# PowerSystem.net
KiCad netlist of a schematic drawn in EAGLE
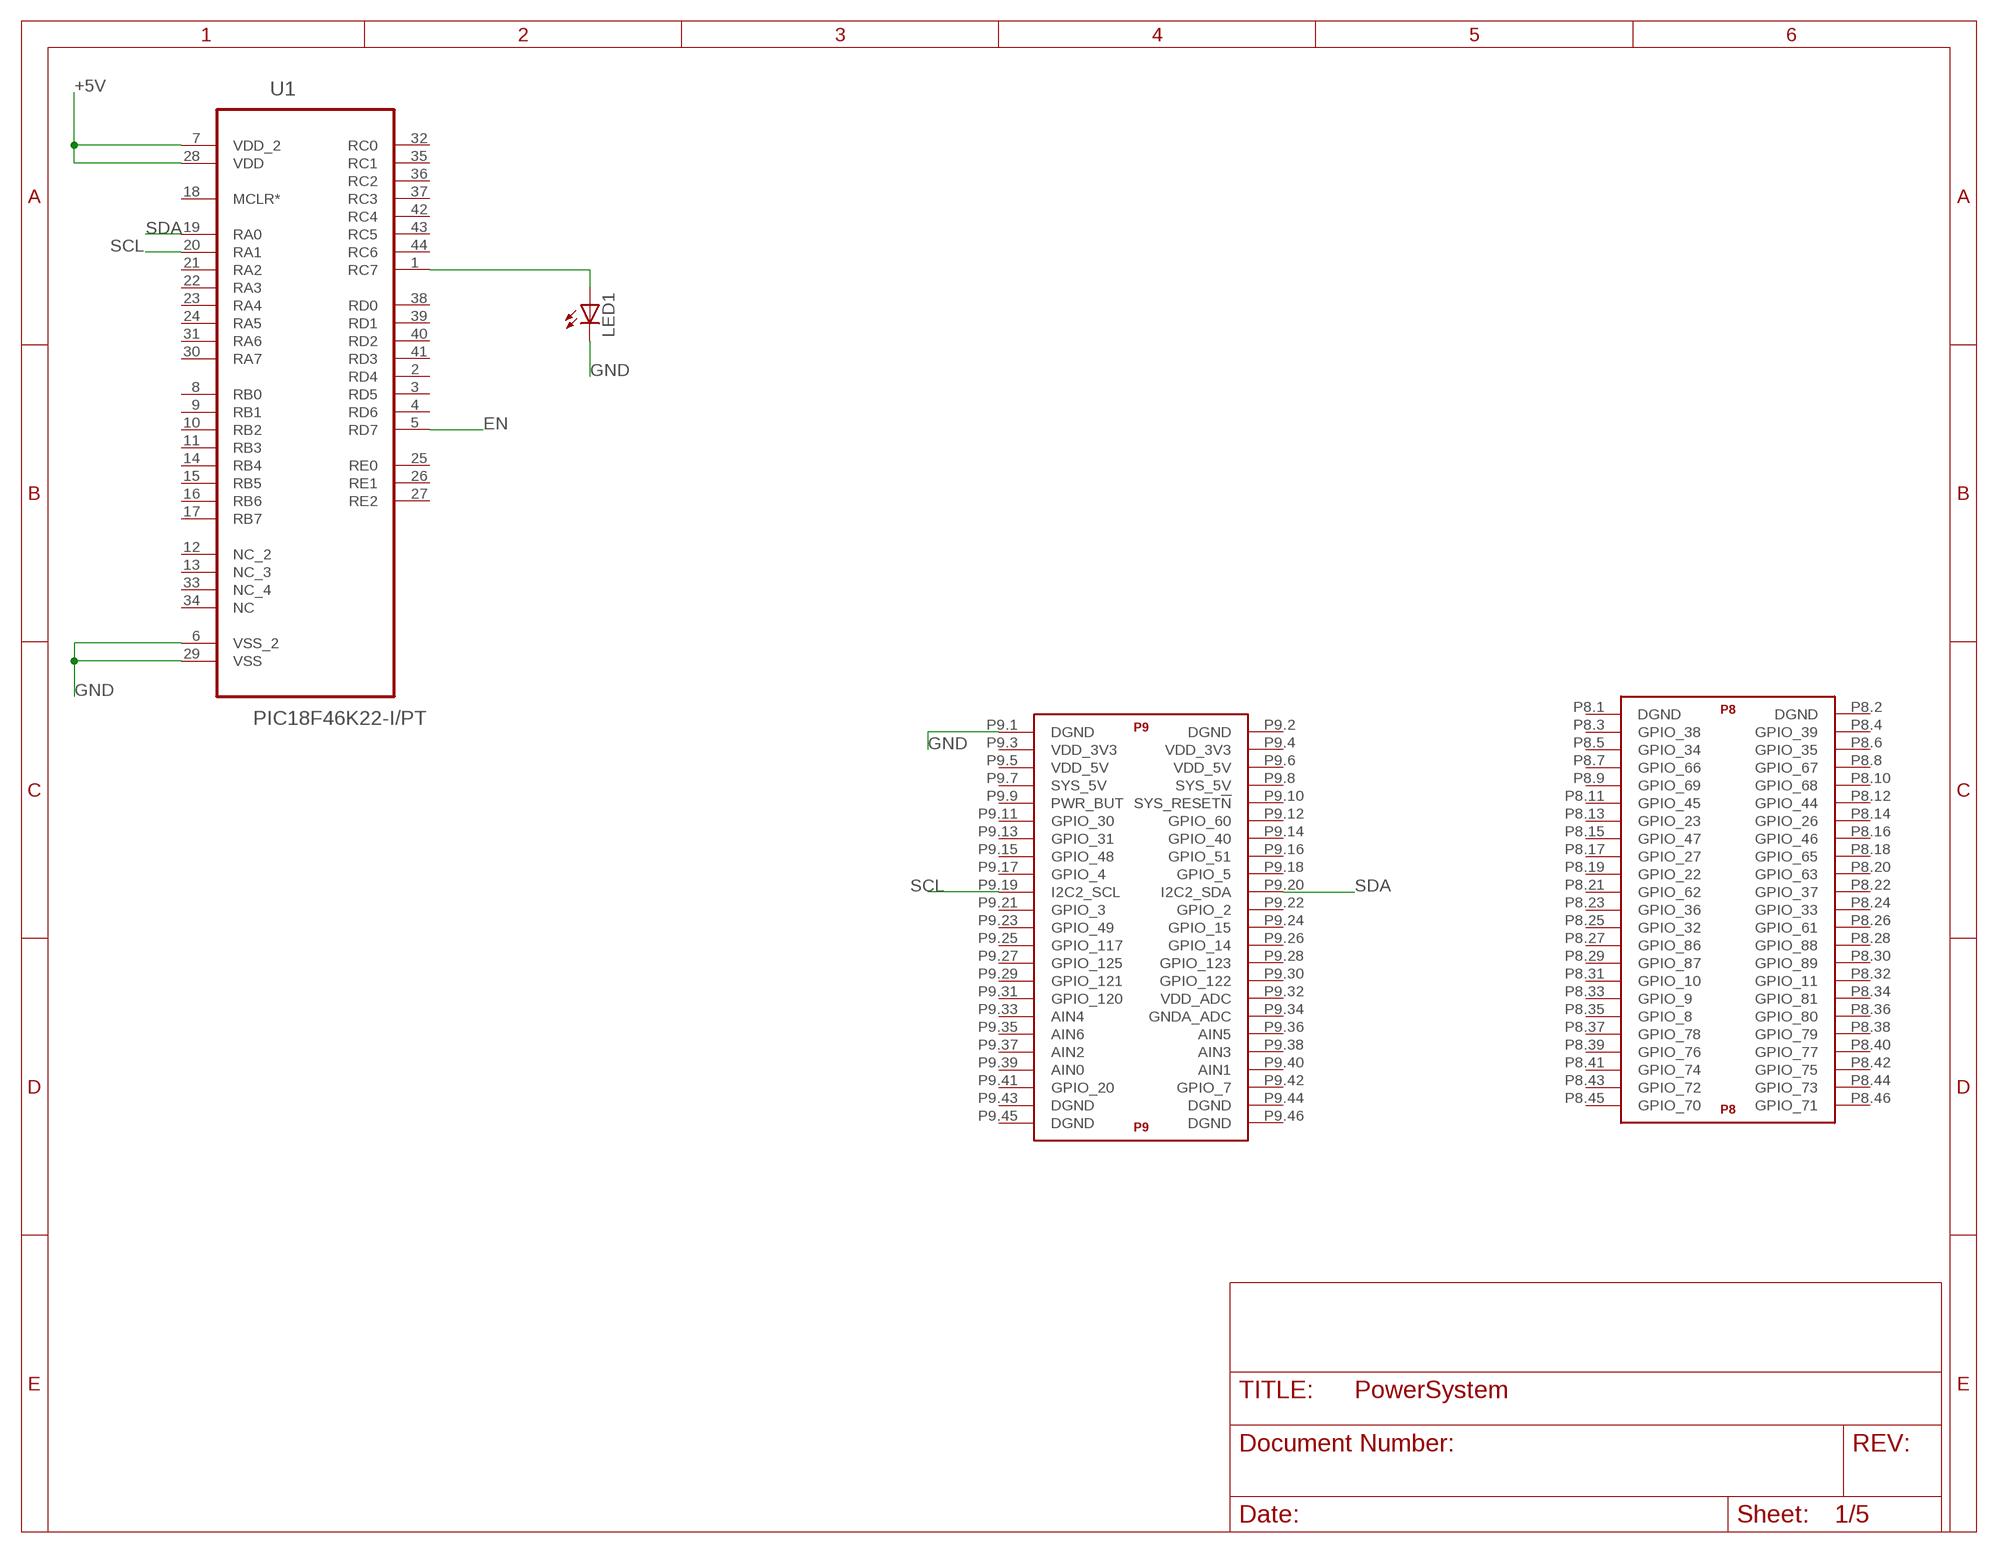
[diagram p0: schematic, sheet 1]
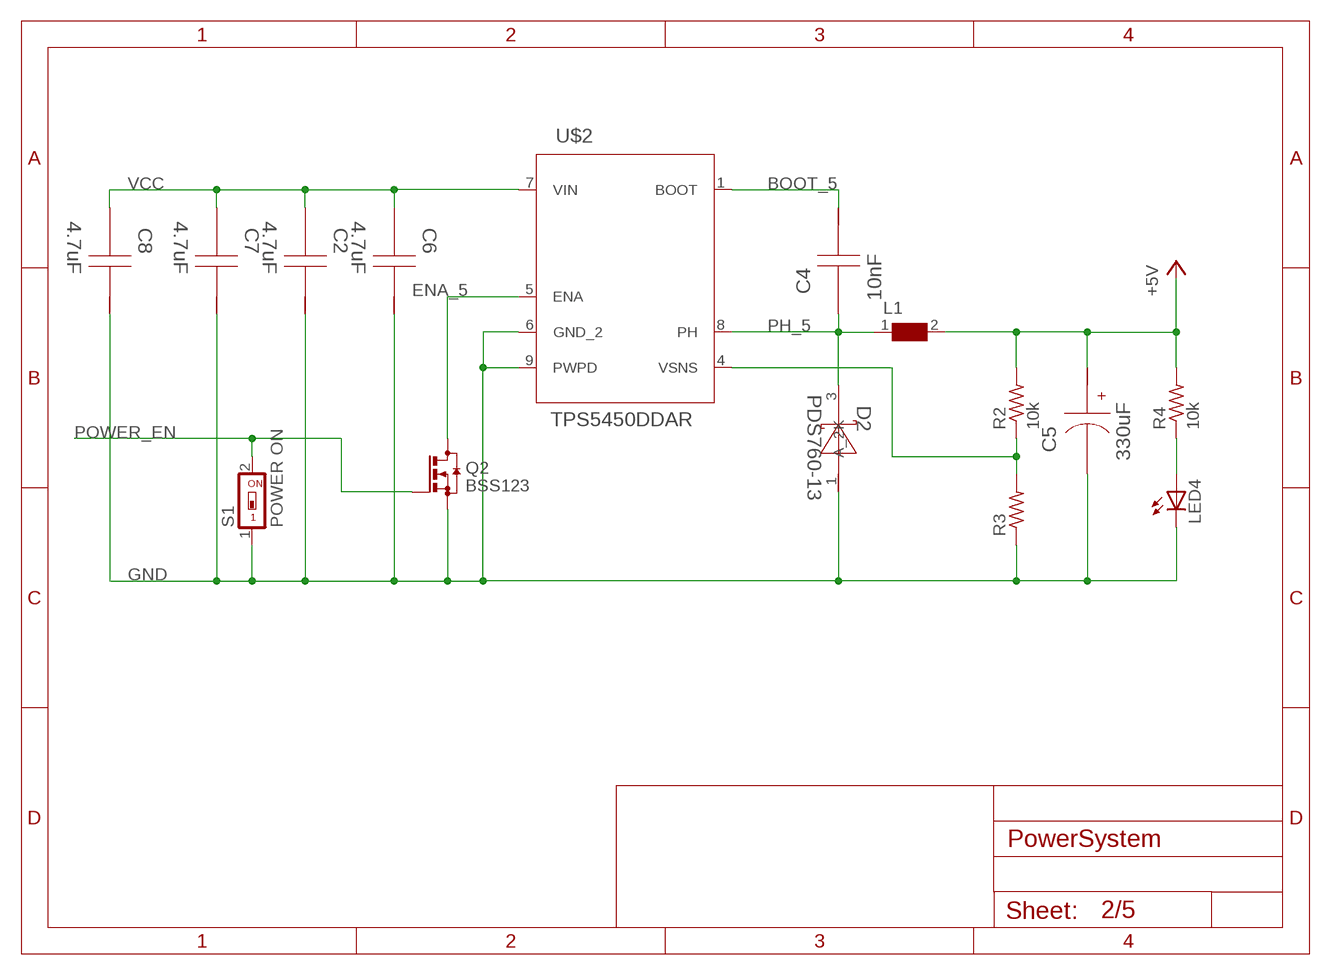
[diagram p1: schematic, sheet 2]
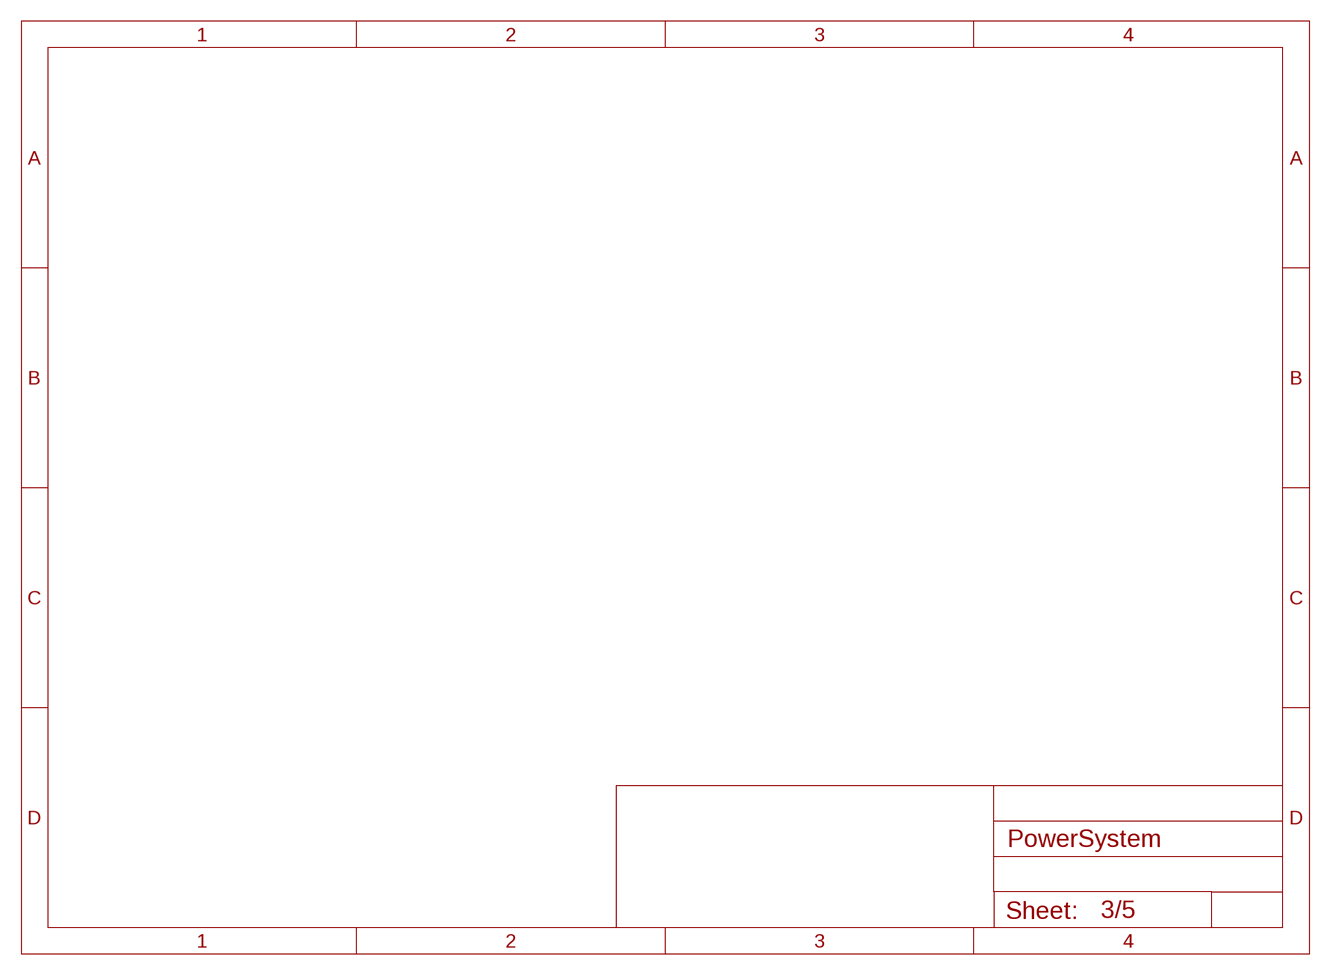
[diagram p2: schematic, sheet 3]
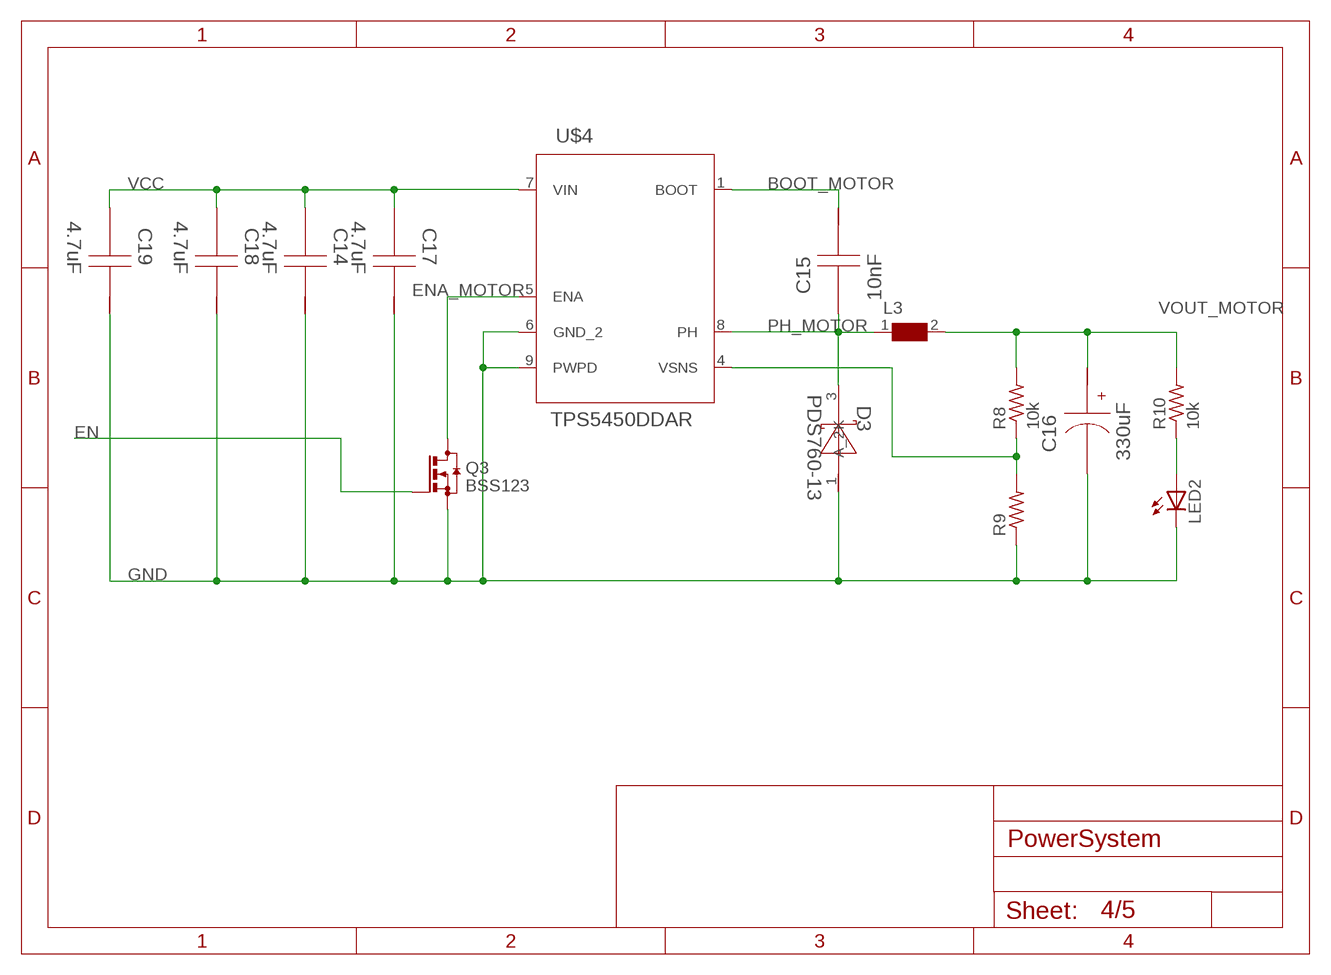
[diagram p3: schematic, sheet 4]
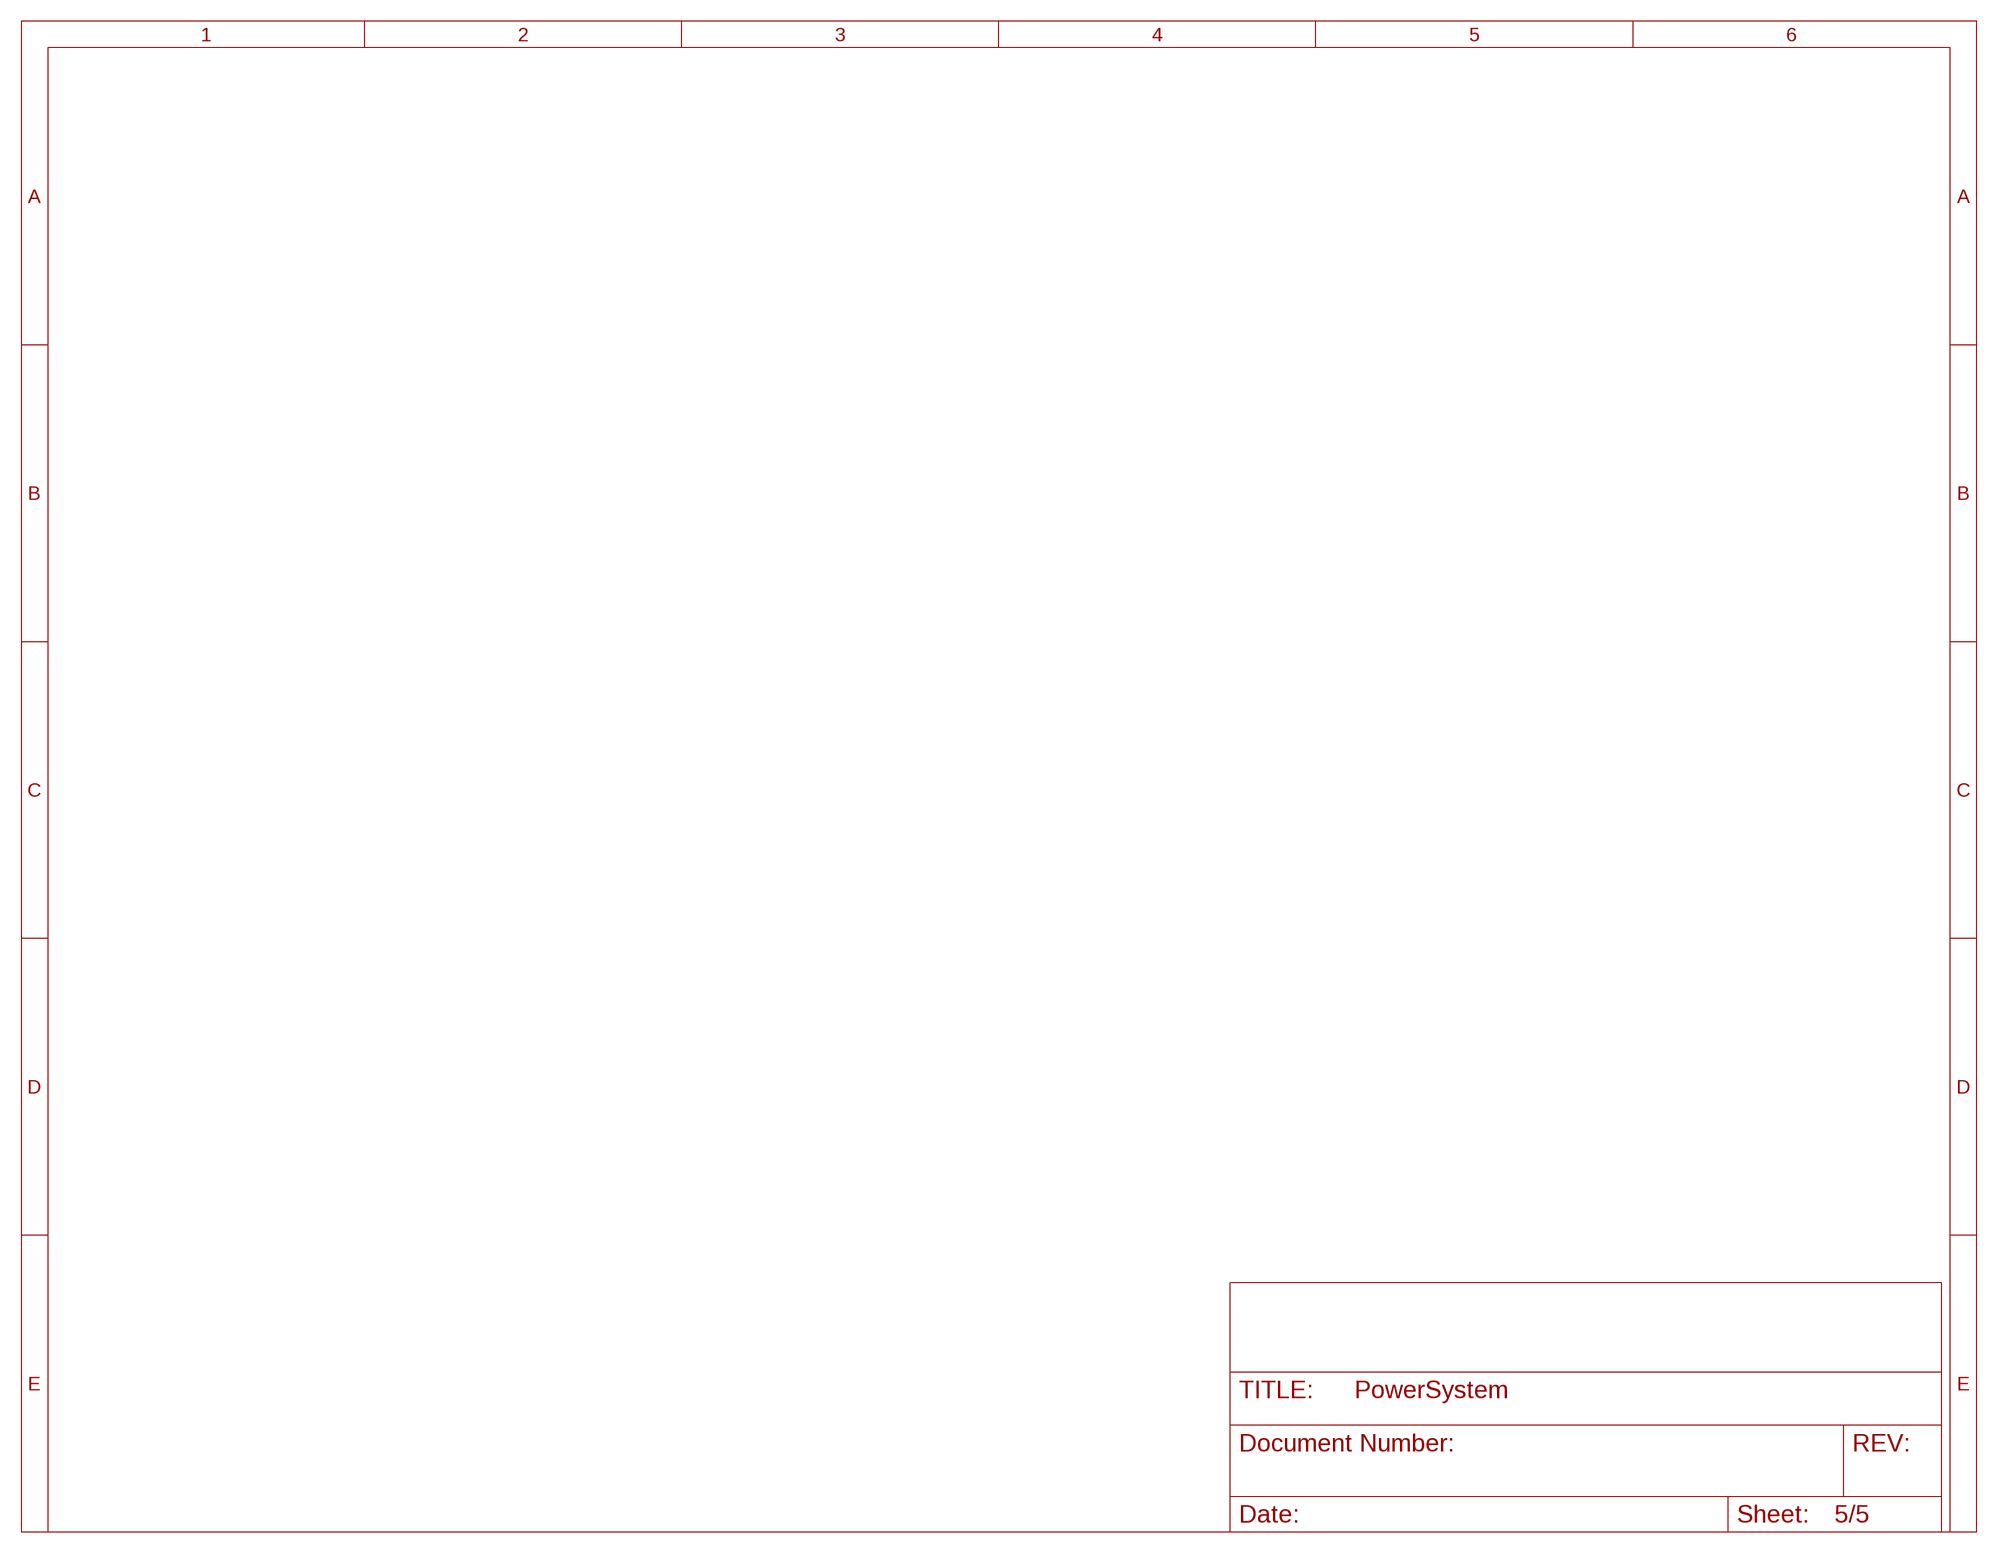
[diagram p4: schematic, sheet 5]

(export (version "E")
  (design (tool "Eeschema 10.0.6"))
  (components
    (comp (ref "C2")
      (value "4.7uF")
      (footprint "eagle-import:1206")
      (fields (field (name "MANUFACTURER_PART_NUMBER") "GRM31CR71H475KA12L"))
      (libsource (lib "eagle-import") (part "GRM31CR71H475KA12L"))
    )
    (comp (ref "C4")
      (value "10nF")
      (footprint "eagle-import:0805")
      (fields (field (name "MANUFACTURER_PART_NUMBER") "C0805C103K5RACTU"))
      (libsource (lib "eagle-import") (part "C0805C103K5RACTU"))
    )
    (comp (ref "C5")
      (value "330uF")
      (footprint "eagle-import:SM_RADIAL_10AMM")
      (fields (field (name "MANUFACTURER_PART_NUMBER") "10SVP330MX"))
      (libsource (lib "eagle-import") (part "10SVP330MX"))
    )
    (comp (ref "C6")
      (value "4.7uF")
      (footprint "eagle-import:1206")
      (fields (field (name "MANUFACTURER_PART_NUMBER") "GRM31CR71H475KA12L"))
      (libsource (lib "eagle-import") (part "GRM31CR71H475KA12L"))
    )
    (comp (ref "C7")
      (value "4.7uF")
      (footprint "eagle-import:1206")
      (fields (field (name "MANUFACTURER_PART_NUMBER") "GRM31CR71H475KA12L"))
      (libsource (lib "eagle-import") (part "GRM31CR71H475KA12L"))
    )
    (comp (ref "C8")
      (value "4.7uF")
      (footprint "eagle-import:1206")
      (fields (field (name "MANUFACTURER_PART_NUMBER") "GRM31CR71H475KA12L"))
      (libsource (lib "eagle-import") (part "GRM31CR71H475KA12L"))
    )
    (comp (ref "D2")
      (value "PDS760-13")
      (footprint "eagle-import:POWERDI5")
      (libsource (lib "eagle-import") (part "PDS760-13"))
    )
    (comp (ref "L1")
      (value "WE-HCC-7443331000_1090")
      (footprint "eagle-import:WE-HCC_1090")
      (fields (field (name "MPN") "7443331000"))
      (libsource (lib "eagle-import") (part "WE-HCC_1090-7443331000"))
    )
    (comp (ref "LED4")
      (value "LEDSML1206")
      (footprint "eagle-import:SML1206")
      (libsource (lib "eagle-import") (part "led_LEDSML1206"))
    )
    (comp (ref "Q2")
      (value "BSS123")
      (footprint "eagle-import:SOT23")
      (libsource (lib "eagle-import") (part "BSS123"))
    )
    (comp (ref "R2")
      (value "10k")
      (footprint "eagle-import:R1206")
      (libsource (lib "eagle-import") (part "R-US_R1206"))
    )
    (comp (ref "R3")
      (value "R-US_R1206")
      (footprint "eagle-import:R1206")
      (libsource (lib "eagle-import") (part "R-US_R1206"))
    )
    (comp (ref "R4")
      (value "10k")
      (footprint "eagle-import:R1206")
      (libsource (lib "eagle-import") (part "R-US_R1206"))
    )
    (comp (ref "S1")
      (value "POWER ON")
      (footprint "eagle-import:SMS-001")
      (libsource (lib "eagle-import") (part "SWS001"))
    )
    (comp (ref "U$2")
      (value "TPS5450DDAR")
      (footprint "eagle-import:R-PDSO-G8")
      (fields (field (name "MANUFACTURER_PART_NUMBER") "TPS5450DDA"))
      (libsource (lib "eagle-import") (part "TPS5450DDAR"))
    )
    (comp (ref "LED1")
      (value "LED")
      (footprint "eagle-import:SMARTLED-TTW")
      (libsource (lib "eagle-import") (part "LED"))
    )
    (comp (ref "U$1")
      (value "BEAGLE_BONE_BLACK_CAPE")
      (footprint "eagle-import:BEAGLE_BONE_BLACK_CAPE")
      (libsource (lib "eagle-import") (part "BEAGLE_BONE_BLACK_CAPE"))
    )
    (comp (ref "U1")
      (value "PIC18F46K22-I/PT")
      (footprint "eagle-import:QFP80P1200X1200X120-44N")
      (libsource (lib "eagle-import") (part "PIC18F46K22-I/PT"))
    )
    (comp (ref "C14")
      (value "4.7uF")
      (footprint "eagle-import:1206")
      (fields (field (name "MANUFACTURER_PART_NUMBER") "GRM31CR71H475KA12L"))
      (libsource (lib "eagle-import") (part "GRM31CR71H475KA12L"))
    )
    (comp (ref "C15")
      (value "10nF")
      (footprint "eagle-import:0805")
      (fields (field (name "MANUFACTURER_PART_NUMBER") "C0805C103K5RACTU"))
      (libsource (lib "eagle-import") (part "C0805C103K5RACTU"))
    )
    (comp (ref "C16")
      (value "330uF")
      (footprint "eagle-import:SM_RADIAL_10AMM")
      (fields (field (name "MANUFACTURER_PART_NUMBER") "10SVP330MX"))
      (libsource (lib "eagle-import") (part "10SVP330MX"))
    )
    (comp (ref "C17")
      (value "4.7uF")
      (footprint "eagle-import:1206")
      (fields (field (name "MANUFACTURER_PART_NUMBER") "GRM31CR71H475KA12L"))
      (libsource (lib "eagle-import") (part "GRM31CR71H475KA12L"))
    )
    (comp (ref "C18")
      (value "4.7uF")
      (footprint "eagle-import:1206")
      (fields (field (name "MANUFACTURER_PART_NUMBER") "GRM31CR71H475KA12L"))
      (libsource (lib "eagle-import") (part "GRM31CR71H475KA12L"))
    )
    (comp (ref "C19")
      (value "4.7uF")
      (footprint "eagle-import:1206")
      (fields (field (name "MANUFACTURER_PART_NUMBER") "GRM31CR71H475KA12L"))
      (libsource (lib "eagle-import") (part "GRM31CR71H475KA12L"))
    )
    (comp (ref "D3")
      (value "PDS760-13")
      (footprint "eagle-import:POWERDI5")
      (libsource (lib "eagle-import") (part "PDS760-13"))
    )
    (comp (ref "L3")
      (value "WE-HCC-7443331000_1090")
      (footprint "eagle-import:WE-HCC_1090")
      (fields (field (name "MPN") "7443331000"))
      (libsource (lib "eagle-import") (part "WE-HCC_1090-7443331000"))
    )
    (comp (ref "LED2")
      (value "LEDSML1206")
      (footprint "eagle-import:SML1206")
      (libsource (lib "eagle-import") (part "led_LEDSML1206"))
    )
    (comp (ref "Q3")
      (value "BSS123")
      (footprint "eagle-import:SOT23")
      (libsource (lib "eagle-import") (part "BSS123"))
    )
    (comp (ref "R8")
      (value "10k")
      (footprint "eagle-import:R1206")
      (libsource (lib "eagle-import") (part "R-US_R1206"))
    )
    (comp (ref "R9")
      (value "R-US_R1206")
      (footprint "eagle-import:R1206")
      (libsource (lib "eagle-import") (part "R-US_R1206"))
    )
    (comp (ref "R10")
      (value "10k")
      (footprint "eagle-import:R1206")
      (libsource (lib "eagle-import") (part "R-US_R1206"))
    )
    (comp (ref "U$4")
      (value "TPS5450DDAR")
      (footprint "eagle-import:R-PDSO-G8")
      (fields (field (name "MANUFACTURER_PART_NUMBER") "TPS5450DDA"))
      (libsource (lib "eagle-import") (part "TPS5450DDAR"))
    )
  )
  (nets
    (net (code "1") (name "+5V") (class "Default")
      (node (ref "C5") (pin "1") (pinfunction "+_1") (pintype "passive"))
      (node (ref "L1") (pin "2") (pinfunction "2_2") (pintype "passive"))
      (node (ref "R2") (pin "2") (pinfunction "2_2") (pintype "passive"))
      (node (ref "R4") (pin "2") (pinfunction "2_2") (pintype "passive"))
      (node (ref "U1") (pin "28") (pinfunction "VDD_28") (pintype "power_in"))
      (node (ref "U1") (pin "7") (pinfunction "VDD_2_7") (pintype "power_in"))
    )
    (net (code "2") (name "BOOT_5") (class "Default")
      (node (ref "C4") (pin "1") (pinfunction "1_1") (pintype "passive"))
      (node (ref "U$2") (pin "1") (pinfunction "BOOT_1") (pintype "passive"))
    )
    (net (code "3") (name "BOOT_MOTOR") (class "Default")
      (node (ref "C15") (pin "1") (pinfunction "1_1") (pintype "passive"))
      (node (ref "U$4") (pin "1") (pinfunction "BOOT_1") (pintype "passive"))
    )
    (net (code "4") (name "EN") (class "Default")
      (node (ref "Q3") (pin "1") (pinfunction "G_1") (pintype "passive"))
      (node (ref "U1") (pin "5") (pinfunction "RD7_5") (pintype "bidirectional"))
    )
    (net (code "5") (name "ENA_5") (class "Default")
      (node (ref "Q2") (pin "3") (pinfunction "D_3") (pintype "passive"))
      (node (ref "U$2") (pin "5") (pinfunction "ENA_5") (pintype "passive"))
    )
    (net (code "6") (name "ENA_MOTOR") (class "Default")
      (node (ref "Q3") (pin "3") (pinfunction "D_3") (pintype "passive"))
      (node (ref "U$4") (pin "5") (pinfunction "ENA_5") (pintype "passive"))
    )
    (net (code "7") (name "GND") (class "Default")
      (node (ref "C14") (pin "1") (pinfunction "1_1") (pintype "passive"))
      (node (ref "C16") (pin "2") (pinfunction "-_2") (pintype "passive"))
      (node (ref "C17") (pin "1") (pinfunction "1_1") (pintype "passive"))
      (node (ref "C18") (pin "1") (pinfunction "1_1") (pintype "passive"))
      (node (ref "C19") (pin "1") (pinfunction "1_1") (pintype "passive"))
      (node (ref "C2") (pin "1") (pinfunction "1_1") (pintype "passive"))
      (node (ref "C5") (pin "2") (pinfunction "-_2") (pintype "passive"))
      (node (ref "C6") (pin "1") (pinfunction "1_1") (pintype "passive"))
      (node (ref "C7") (pin "1") (pinfunction "1_1") (pintype "passive"))
      (node (ref "C8") (pin "1") (pinfunction "1_1") (pintype "passive"))
      (node (ref "D2") (pin "1") (pinfunction "A_2_1") (pintype "passive"))
      (node (ref "D3") (pin "1") (pinfunction "A_2_1") (pintype "passive"))
      (node (ref "LED1") (pin "C@1") (pinfunction "C_C@1") (pintype "passive"))
      (node (ref "LED2") (pin "C") (pinfunction "C_C") (pintype "passive"))
      (node (ref "LED4") (pin "C") (pinfunction "C_C") (pintype "passive"))
      (node (ref "Q2") (pin "2") (pinfunction "S_2") (pintype "passive"))
      (node (ref "Q3") (pin "2") (pinfunction "S_2") (pintype "passive"))
      (node (ref "R3") (pin "1") (pinfunction "1_1") (pintype "passive"))
      (node (ref "R9") (pin "1") (pinfunction "1_1") (pintype "passive"))
      (node (ref "S1") (pin "1") (pinfunction "1_1") (pintype "passive"))
      (node (ref "U$1") (pin "P9.1") (pinfunction "DGND_P9.1") (pintype "bidirectional"))
      (node (ref "U$2") (pin "6") (pinfunction "GND_2_6") (pintype "passive"))
      (node (ref "U$2") (pin "9") (pinfunction "PWPD_9") (pintype "passive"))
      (node (ref "U$4") (pin "6") (pinfunction "GND_2_6") (pintype "passive"))
      (node (ref "U$4") (pin "9") (pinfunction "PWPD_9") (pintype "passive"))
      (node (ref "U1") (pin "29") (pinfunction "VSS_29") (pintype "power_in"))
      (node (ref "U1") (pin "6") (pinfunction "VSS_2_6") (pintype "power_in"))
    )
    (net (code "8") (name "Net-(LED1-A)") (class "Default")
      (node (ref "LED1") (pin "A@1") (pinfunction "A_A@1") (pintype "passive"))
      (node (ref "U1") (pin "1") (pinfunction "RC7_1") (pintype "bidirectional"))
    )
    (net (code "9") (name "Net-(LED2-PadA)") (class "Default")
      (node (ref "LED2") (pin "A") (pinfunction "A_A") (pintype "passive"))
      (node (ref "R10") (pin "1") (pinfunction "1_1") (pintype "passive"))
    )
    (net (code "10") (name "Net-(LED4-PadA)") (class "Default")
      (node (ref "LED4") (pin "A") (pinfunction "A_A") (pintype "passive"))
      (node (ref "R4") (pin "1") (pinfunction "1_1") (pintype "passive"))
    )
    (net (code "11") (name "Net-(U$2-VSNS)") (class "Default")
      (node (ref "R2") (pin "1") (pinfunction "1_1") (pintype "passive"))
      (node (ref "R3") (pin "2") (pinfunction "2_2") (pintype "passive"))
      (node (ref "U$2") (pin "4") (pinfunction "VSNS_4") (pintype "passive"))
    )
    (net (code "12") (name "Net-(U$4-VSNS)") (class "Default")
      (node (ref "R8") (pin "1") (pinfunction "1_1") (pintype "passive"))
      (node (ref "R9") (pin "2") (pinfunction "2_2") (pintype "passive"))
      (node (ref "U$4") (pin "4") (pinfunction "VSNS_4") (pintype "passive"))
    )
    (net (code "13") (name "PH_5") (class "Default")
      (node (ref "C4") (pin "2") (pinfunction "2_2") (pintype "passive"))
      (node (ref "D2") (pin "3") (pinfunction "K_3") (pintype "passive"))
      (node (ref "L1") (pin "1") (pinfunction "1_1") (pintype "passive"))
      (node (ref "U$2") (pin "8") (pinfunction "PH_8") (pintype "passive"))
    )
    (net (code "14") (name "PH_MOTOR") (class "Default")
      (node (ref "C15") (pin "2") (pinfunction "2_2") (pintype "passive"))
      (node (ref "D3") (pin "3") (pinfunction "K_3") (pintype "passive"))
      (node (ref "L3") (pin "1") (pinfunction "1_1") (pintype "passive"))
      (node (ref "U$4") (pin "8") (pinfunction "PH_8") (pintype "passive"))
    )
    (net (code "15") (name "POWER_EN") (class "Default")
      (node (ref "Q2") (pin "1") (pinfunction "G_1") (pintype "passive"))
      (node (ref "S1") (pin "2") (pinfunction "2_2") (pintype "passive"))
    )
    (net (code "16") (name "SCL") (class "Default")
      (node (ref "U$1") (pin "P9.19") (pinfunction "I2C2_SCL_P9.19") (pintype "bidirectional"))
      (node (ref "U1") (pin "20") (pinfunction "RA1_20") (pintype "bidirectional"))
    )
    (net (code "17") (name "SDA") (class "Default")
      (node (ref "U$1") (pin "P9.20") (pinfunction "I2C2_SDA_P9.20") (pintype "bidirectional"))
      (node (ref "U1") (pin "19") (pinfunction "RA0_19") (pintype "bidirectional"))
    )
    (net (code "18") (name "VCC") (class "Default")
      (node (ref "C14") (pin "2") (pinfunction "2_2") (pintype "passive"))
      (node (ref "C17") (pin "2") (pinfunction "2_2") (pintype "passive"))
      (node (ref "C18") (pin "2") (pinfunction "2_2") (pintype "passive"))
      (node (ref "C19") (pin "2") (pinfunction "2_2") (pintype "passive"))
      (node (ref "C2") (pin "2") (pinfunction "2_2") (pintype "passive"))
      (node (ref "C6") (pin "2") (pinfunction "2_2") (pintype "passive"))
      (node (ref "C7") (pin "2") (pinfunction "2_2") (pintype "passive"))
      (node (ref "C8") (pin "2") (pinfunction "2_2") (pintype "passive"))
      (node (ref "U$2") (pin "7") (pinfunction "VIN_7") (pintype "passive"))
      (node (ref "U$4") (pin "7") (pinfunction "VIN_7") (pintype "passive"))
    )
    (net (code "19") (name "VOUT_MOTOR") (class "Default")
      (node (ref "C16") (pin "1") (pinfunction "+_1") (pintype "passive"))
      (node (ref "L3") (pin "2") (pinfunction "2_2") (pintype "passive"))
      (node (ref "R10") (pin "2") (pinfunction "2_2") (pintype "passive"))
      (node (ref "R8") (pin "2") (pinfunction "2_2") (pintype "passive"))
    )
    (net (code "20") (name "unconnected-(U$1A-DGND-PadP8.1)") (class "Default")
      (node (ref "U$1") (pin "P8.1") (pinfunction "DGND_P8.1") (pintype "bidirectional"))
    )
    (net (code "21") (name "unconnected-(U$1A-DGND-PadP8.2)") (class "Default")
      (node (ref "U$1") (pin "P8.2") (pinfunction "DGND_P8.2") (pintype "bidirectional"))
    )
    (net (code "22") (name "unconnected-(U$1A-GPIO_8-PadP8.35)") (class "Default")
      (node (ref "U$1") (pin "P8.35") (pinfunction "GPIO_8_P8.35") (pintype "bidirectional"))
    )
    (net (code "23") (name "unconnected-(U$1A-GPIO_9-PadP8.33)") (class "Default")
      (node (ref "U$1") (pin "P8.33") (pinfunction "GPIO_9_P8.33") (pintype "bidirectional"))
    )
    (net (code "24") (name "unconnected-(U$1A-GPIO_10-PadP8.31)") (class "Default")
      (node (ref "U$1") (pin "P8.31") (pinfunction "GPIO_10_P8.31") (pintype "bidirectional"))
    )
    (net (code "25") (name "unconnected-(U$1A-GPIO_11-PadP8.32)") (class "Default")
      (node (ref "U$1") (pin "P8.32") (pinfunction "GPIO_11_P8.32") (pintype "bidirectional"))
    )
    (net (code "26") (name "unconnected-(U$1A-GPIO_22-PadP8.19)") (class "Default")
      (node (ref "U$1") (pin "P8.19") (pinfunction "GPIO_22_P8.19") (pintype "bidirectional"))
    )
    (net (code "27") (name "unconnected-(U$1A-GPIO_23-PadP8.13)") (class "Default")
      (node (ref "U$1") (pin "P8.13") (pinfunction "GPIO_23_P8.13") (pintype "bidirectional"))
    )
    (net (code "28") (name "unconnected-(U$1A-GPIO_26-PadP8.14)") (class "Default")
      (node (ref "U$1") (pin "P8.14") (pinfunction "GPIO_26_P8.14") (pintype "bidirectional"))
    )
    (net (code "29") (name "unconnected-(U$1A-GPIO_27-PadP8.17)") (class "Default")
      (node (ref "U$1") (pin "P8.17") (pinfunction "GPIO_27_P8.17") (pintype "bidirectional"))
    )
    (net (code "30") (name "unconnected-(U$1A-GPIO_32-PadP8.25)") (class "Default")
      (node (ref "U$1") (pin "P8.25") (pinfunction "GPIO_32_P8.25") (pintype "bidirectional"))
    )
    (net (code "31") (name "unconnected-(U$1A-GPIO_33-PadP8.24)") (class "Default")
      (node (ref "U$1") (pin "P8.24") (pinfunction "GPIO_33_P8.24") (pintype "bidirectional"))
    )
    (net (code "32") (name "unconnected-(U$1A-GPIO_34-PadP8.5)") (class "Default")
      (node (ref "U$1") (pin "P8.5") (pinfunction "GPIO_34_P8.5") (pintype "bidirectional"))
    )
    (net (code "33") (name "unconnected-(U$1A-GPIO_35-PadP8.6)") (class "Default")
      (node (ref "U$1") (pin "P8.6") (pinfunction "GPIO_35_P8.6") (pintype "bidirectional"))
    )
    (net (code "34") (name "unconnected-(U$1A-GPIO_36-PadP8.23)") (class "Default")
      (node (ref "U$1") (pin "P8.23") (pinfunction "GPIO_36_P8.23") (pintype "bidirectional"))
    )
    (net (code "35") (name "unconnected-(U$1A-GPIO_37-PadP8.22)") (class "Default")
      (node (ref "U$1") (pin "P8.22") (pinfunction "GPIO_37_P8.22") (pintype "bidirectional"))
    )
    (net (code "36") (name "unconnected-(U$1A-GPIO_38-PadP8.3)") (class "Default")
      (node (ref "U$1") (pin "P8.3") (pinfunction "GPIO_38_P8.3") (pintype "bidirectional"))
    )
    (net (code "37") (name "unconnected-(U$1A-GPIO_39-PadP8.4)") (class "Default")
      (node (ref "U$1") (pin "P8.4") (pinfunction "GPIO_39_P8.4") (pintype "bidirectional"))
    )
    (net (code "38") (name "unconnected-(U$1A-GPIO_44-PadP8.12)") (class "Default")
      (node (ref "U$1") (pin "P8.12") (pinfunction "GPIO_44_P8.12") (pintype "bidirectional"))
    )
    (net (code "39") (name "unconnected-(U$1A-GPIO_45-PadP8.11)") (class "Default")
      (node (ref "U$1") (pin "P8.11") (pinfunction "GPIO_45_P8.11") (pintype "bidirectional"))
    )
    (net (code "40") (name "unconnected-(U$1A-GPIO_46-PadP8.16)") (class "Default")
      (node (ref "U$1") (pin "P8.16") (pinfunction "GPIO_46_P8.16") (pintype "bidirectional"))
    )
    (net (code "41") (name "unconnected-(U$1A-GPIO_47-PadP8.15)") (class "Default")
      (node (ref "U$1") (pin "P8.15") (pinfunction "GPIO_47_P8.15") (pintype "bidirectional"))
    )
    (net (code "42") (name "unconnected-(U$1A-GPIO_61-PadP8.26)") (class "Default")
      (node (ref "U$1") (pin "P8.26") (pinfunction "GPIO_61_P8.26") (pintype "bidirectional"))
    )
    (net (code "43") (name "unconnected-(U$1A-GPIO_62-PadP8.21)") (class "Default")
      (node (ref "U$1") (pin "P8.21") (pinfunction "GPIO_62_P8.21") (pintype "bidirectional"))
    )
    (net (code "44") (name "unconnected-(U$1A-GPIO_63-PadP8.20)") (class "Default")
      (node (ref "U$1") (pin "P8.20") (pinfunction "GPIO_63_P8.20") (pintype "bidirectional"))
    )
    (net (code "45") (name "unconnected-(U$1A-GPIO_65-PadP8.18)") (class "Default")
      (node (ref "U$1") (pin "P8.18") (pinfunction "GPIO_65_P8.18") (pintype "bidirectional"))
    )
    (net (code "46") (name "unconnected-(U$1A-GPIO_66-PadP8.7)") (class "Default")
      (node (ref "U$1") (pin "P8.7") (pinfunction "GPIO_66_P8.7") (pintype "bidirectional"))
    )
    (net (code "47") (name "unconnected-(U$1A-GPIO_67-PadP8.8)") (class "Default")
      (node (ref "U$1") (pin "P8.8") (pinfunction "GPIO_67_P8.8") (pintype "bidirectional"))
    )
    (net (code "48") (name "unconnected-(U$1A-GPIO_68-PadP8.10)") (class "Default")
      (node (ref "U$1") (pin "P8.10") (pinfunction "GPIO_68_P8.10") (pintype "bidirectional"))
    )
    (net (code "49") (name "unconnected-(U$1A-GPIO_69-PadP8.9)") (class "Default")
      (node (ref "U$1") (pin "P8.9") (pinfunction "GPIO_69_P8.9") (pintype "bidirectional"))
    )
    (net (code "50") (name "unconnected-(U$1A-GPIO_70-PadP8.45)") (class "Default")
      (node (ref "U$1") (pin "P8.45") (pinfunction "GPIO_70_P8.45") (pintype "bidirectional"))
    )
    (net (code "51") (name "unconnected-(U$1A-GPIO_71-PadP8.46)") (class "Default")
      (node (ref "U$1") (pin "P8.46") (pinfunction "GPIO_71_P8.46") (pintype "bidirectional"))
    )
    (net (code "52") (name "unconnected-(U$1A-GPIO_72-PadP8.43)") (class "Default")
      (node (ref "U$1") (pin "P8.43") (pinfunction "GPIO_72_P8.43") (pintype "bidirectional"))
    )
    (net (code "53") (name "unconnected-(U$1A-GPIO_73-PadP8.44)") (class "Default")
      (node (ref "U$1") (pin "P8.44") (pinfunction "GPIO_73_P8.44") (pintype "bidirectional"))
    )
    (net (code "54") (name "unconnected-(U$1A-GPIO_74-PadP8.41)") (class "Default")
      (node (ref "U$1") (pin "P8.41") (pinfunction "GPIO_74_P8.41") (pintype "bidirectional"))
    )
    (net (code "55") (name "unconnected-(U$1A-GPIO_75-PadP8.42)") (class "Default")
      (node (ref "U$1") (pin "P8.42") (pinfunction "GPIO_75_P8.42") (pintype "bidirectional"))
    )
    (net (code "56") (name "unconnected-(U$1A-GPIO_76-PadP8.39)") (class "Default")
      (node (ref "U$1") (pin "P8.39") (pinfunction "GPIO_76_P8.39") (pintype "bidirectional"))
    )
    (net (code "57") (name "unconnected-(U$1A-GPIO_77-PadP8.40)") (class "Default")
      (node (ref "U$1") (pin "P8.40") (pinfunction "GPIO_77_P8.40") (pintype "bidirectional"))
    )
    (net (code "58") (name "unconnected-(U$1A-GPIO_78-PadP8.37)") (class "Default")
      (node (ref "U$1") (pin "P8.37") (pinfunction "GPIO_78_P8.37") (pintype "bidirectional"))
    )
    (net (code "59") (name "unconnected-(U$1A-GPIO_79-PadP8.38)") (class "Default")
      (node (ref "U$1") (pin "P8.38") (pinfunction "GPIO_79_P8.38") (pintype "bidirectional"))
    )
    (net (code "60") (name "unconnected-(U$1A-GPIO_80-PadP8.36)") (class "Default")
      (node (ref "U$1") (pin "P8.36") (pinfunction "GPIO_80_P8.36") (pintype "bidirectional"))
    )
    (net (code "61") (name "unconnected-(U$1A-GPIO_81-PadP8.34)") (class "Default")
      (node (ref "U$1") (pin "P8.34") (pinfunction "GPIO_81_P8.34") (pintype "bidirectional"))
    )
    (net (code "62") (name "unconnected-(U$1A-GPIO_86-PadP8.27)") (class "Default")
      (node (ref "U$1") (pin "P8.27") (pinfunction "GPIO_86_P8.27") (pintype "bidirectional"))
    )
    (net (code "63") (name "unconnected-(U$1A-GPIO_87-PadP8.29)") (class "Default")
      (node (ref "U$1") (pin "P8.29") (pinfunction "GPIO_87_P8.29") (pintype "bidirectional"))
    )
    (net (code "64") (name "unconnected-(U$1A-GPIO_88-PadP8.28)") (class "Default")
      (node (ref "U$1") (pin "P8.28") (pinfunction "GPIO_88_P8.28") (pintype "bidirectional"))
    )
    (net (code "65") (name "unconnected-(U$1A-GPIO_89-PadP8.30)") (class "Default")
      (node (ref "U$1") (pin "P8.30") (pinfunction "GPIO_89_P8.30") (pintype "bidirectional"))
    )
    (net (code "66") (name "unconnected-(U$1B-AIN0-PadP9.39)") (class "Default")
      (node (ref "U$1") (pin "P9.39") (pinfunction "AIN0_P9.39") (pintype "bidirectional"))
    )
    (net (code "67") (name "unconnected-(U$1B-AIN1-PadP9.40)") (class "Default")
      (node (ref "U$1") (pin "P9.40") (pinfunction "AIN1_P9.40") (pintype "bidirectional"))
    )
    (net (code "68") (name "unconnected-(U$1B-AIN2-PadP9.37)") (class "Default")
      (node (ref "U$1") (pin "P9.37") (pinfunction "AIN2_P9.37") (pintype "bidirectional"))
    )
    (net (code "69") (name "unconnected-(U$1B-AIN3-PadP9.38)") (class "Default")
      (node (ref "U$1") (pin "P9.38") (pinfunction "AIN3_P9.38") (pintype "bidirectional"))
    )
    (net (code "70") (name "unconnected-(U$1B-AIN4-PadP9.33)") (class "Default")
      (node (ref "U$1") (pin "P9.33") (pinfunction "AIN4_P9.33") (pintype "bidirectional"))
    )
    (net (code "71") (name "unconnected-(U$1B-AIN5-PadP9.36)") (class "Default")
      (node (ref "U$1") (pin "P9.36") (pinfunction "AIN5_P9.36") (pintype "bidirectional"))
    )
    (net (code "72") (name "unconnected-(U$1B-AIN6-PadP9.35)") (class "Default")
      (node (ref "U$1") (pin "P9.35") (pinfunction "AIN6_P9.35") (pintype "bidirectional"))
    )
    (net (code "73") (name "unconnected-(U$1B-DGND-PadP9.2)") (class "Default")
      (node (ref "U$1") (pin "P9.2") (pinfunction "DGND_P9.2") (pintype "bidirectional"))
    )
    (net (code "74") (name "unconnected-(U$1B-DGND-PadP9.43)") (class "Default")
      (node (ref "U$1") (pin "P9.43") (pinfunction "DGND_P9.43") (pintype "bidirectional"))
    )
    (net (code "75") (name "unconnected-(U$1B-DGND-PadP9.44)") (class "Default")
      (node (ref "U$1") (pin "P9.44") (pinfunction "DGND_P9.44") (pintype "bidirectional"))
    )
    (net (code "76") (name "unconnected-(U$1B-DGND-PadP9.45)") (class "Default")
      (node (ref "U$1") (pin "P9.45") (pinfunction "DGND_P9.45") (pintype "bidirectional"))
    )
    (net (code "77") (name "unconnected-(U$1B-DGND-PadP9.46)") (class "Default")
      (node (ref "U$1") (pin "P9.46") (pinfunction "DGND_P9.46") (pintype "bidirectional"))
    )
    (net (code "78") (name "unconnected-(U$1B-GNDA_ADC-PadP9.34)") (class "Default")
      (node (ref "U$1") (pin "P9.34") (pinfunction "GNDA_ADC_P9.34") (pintype "bidirectional"))
    )
    (net (code "79") (name "unconnected-(U$1B-GPIO_2-PadP9.22)") (class "Default")
      (node (ref "U$1") (pin "P9.22") (pinfunction "GPIO_2_P9.22") (pintype "bidirectional"))
    )
    (net (code "80") (name "unconnected-(U$1B-GPIO_3-PadP9.21)") (class "Default")
      (node (ref "U$1") (pin "P9.21") (pinfunction "GPIO_3_P9.21") (pintype "bidirectional"))
    )
    (net (code "81") (name "unconnected-(U$1B-GPIO_4-PadP9.17)") (class "Default")
      (node (ref "U$1") (pin "P9.17") (pinfunction "GPIO_4_P9.17") (pintype "bidirectional"))
    )
    (net (code "82") (name "unconnected-(U$1B-GPIO_5-PadP9.18)") (class "Default")
      (node (ref "U$1") (pin "P9.18") (pinfunction "GPIO_5_P9.18") (pintype "bidirectional"))
    )
    (net (code "83") (name "unconnected-(U$1B-GPIO_7-PadP9.42)") (class "Default")
      (node (ref "U$1") (pin "P9.42") (pinfunction "GPIO_7_P9.42") (pintype "bidirectional"))
    )
    (net (code "84") (name "unconnected-(U$1B-GPIO_14-PadP9.26)") (class "Default")
      (node (ref "U$1") (pin "P9.26") (pinfunction "GPIO_14_P9.26") (pintype "bidirectional"))
    )
    (net (code "85") (name "unconnected-(U$1B-GPIO_15-PadP9.24)") (class "Default")
      (node (ref "U$1") (pin "P9.24") (pinfunction "GPIO_15_P9.24") (pintype "bidirectional"))
    )
    (net (code "86") (name "unconnected-(U$1B-GPIO_20-PadP9.41)") (class "Default")
      (node (ref "U$1") (pin "P9.41") (pinfunction "GPIO_20_P9.41") (pintype "bidirectional"))
    )
    (net (code "87") (name "unconnected-(U$1B-GPIO_30-PadP9.11)") (class "Default")
      (node (ref "U$1") (pin "P9.11") (pinfunction "GPIO_30_P9.11") (pintype "bidirectional"))
    )
    (net (code "88") (name "unconnected-(U$1B-GPIO_31-PadP9.13)") (class "Default")
      (node (ref "U$1") (pin "P9.13") (pinfunction "GPIO_31_P9.13") (pintype "bidirectional"))
    )
    (net (code "89") (name "unconnected-(U$1B-GPIO_40-PadP9.14)") (class "Default")
      (node (ref "U$1") (pin "P9.14") (pinfunction "GPIO_40_P9.14") (pintype "bidirectional"))
    )
    (net (code "90") (name "unconnected-(U$1B-GPIO_48-PadP9.15)") (class "Default")
      (node (ref "U$1") (pin "P9.15") (pinfunction "GPIO_48_P9.15") (pintype "bidirectional"))
    )
    (net (code "91") (name "unconnected-(U$1B-GPIO_49-PadP9.23)") (class "Default")
      (node (ref "U$1") (pin "P9.23") (pinfunction "GPIO_49_P9.23") (pintype "bidirectional"))
    )
    (net (code "92") (name "unconnected-(U$1B-GPIO_51-PadP9.16)") (class "Default")
      (node (ref "U$1") (pin "P9.16") (pinfunction "GPIO_51_P9.16") (pintype "bidirectional"))
    )
    (net (code "93") (name "unconnected-(U$1B-GPIO_60-PadP9.12)") (class "Default")
      (node (ref "U$1") (pin "P9.12") (pinfunction "GPIO_60_P9.12") (pintype "bidirectional"))
    )
    (net (code "94") (name "unconnected-(U$1B-GPIO_117-PadP9.25)") (class "Default")
      (node (ref "U$1") (pin "P9.25") (pinfunction "GPIO_117_P9.25") (pintype "bidirectional"))
    )
    (net (code "95") (name "unconnected-(U$1B-GPIO_120-PadP9.31)") (class "Default")
      (node (ref "U$1") (pin "P9.31") (pinfunction "GPIO_120_P9.31") (pintype "bidirectional"))
    )
    (net (code "96") (name "unconnected-(U$1B-GPIO_121-PadP9.29)") (class "Default")
      (node (ref "U$1") (pin "P9.29") (pinfunction "GPIO_121_P9.29") (pintype "bidirectional"))
    )
    (net (code "97") (name "unconnected-(U$1B-GPIO_122-PadP9.30)") (class "Default")
      (node (ref "U$1") (pin "P9.30") (pinfunction "GPIO_122_P9.30") (pintype "bidirectional"))
    )
    (net (code "98") (name "unconnected-(U$1B-GPIO_123-PadP9.28)") (class "Default")
      (node (ref "U$1") (pin "P9.28") (pinfunction "GPIO_123_P9.28") (pintype "bidirectional"))
    )
    (net (code "99") (name "unconnected-(U$1B-GPIO_125-PadP9.27)") (class "Default")
      (node (ref "U$1") (pin "P9.27") (pinfunction "GPIO_125_P9.27") (pintype "bidirectional"))
    )
    (net (code "100") (name "unconnected-(U$1B-PWR_BUT-PadP9.9)") (class "Default")
      (node (ref "U$1") (pin "P9.9") (pinfunction "PWR_BUT_P9.9") (pintype "bidirectional"))
    )
    (net (code "101") (name "unconnected-(U$1B-SYS_5V-PadP9.7)") (class "Default")
      (node (ref "U$1") (pin "P9.7") (pinfunction "SYS_5V_P9.7") (pintype "bidirectional"))
    )
    (net (code "102") (name "unconnected-(U$1B-SYS_5V-PadP9.8)") (class "Default")
      (node (ref "U$1") (pin "P9.8") (pinfunction "SYS_5V_P9.8") (pintype "bidirectional"))
    )
    (net (code "103") (name "unconnected-(U$1B-SYS_RESET~{N}-PadP9.10)") (class "Default")
      (node (ref "U$1") (pin "P9.10") (pinfunction "SYS_RESET~{N}_P9.10") (pintype "bidirectional"))
    )
    (net (code "104") (name "unconnected-(U$1B-VDD_3V3-PadP9.3)") (class "Default")
      (node (ref "U$1") (pin "P9.3") (pinfunction "VDD_3V3_P9.3") (pintype "bidirectional"))
    )
    (net (code "105") (name "unconnected-(U$1B-VDD_3V3-PadP9.4)") (class "Default")
      (node (ref "U$1") (pin "P9.4") (pinfunction "VDD_3V3_P9.4") (pintype "bidirectional"))
    )
    (net (code "106") (name "unconnected-(U$1B-VDD_5V-PadP9.5)") (class "Default")
      (node (ref "U$1") (pin "P9.5") (pinfunction "VDD_5V_P9.5") (pintype "bidirectional"))
    )
    (net (code "107") (name "unconnected-(U$1B-VDD_5V-PadP9.6)") (class "Default")
      (node (ref "U$1") (pin "P9.6") (pinfunction "VDD_5V_P9.6") (pintype "bidirectional"))
    )
    (net (code "108") (name "unconnected-(U$1B-VDD_ADC-PadP9.32)") (class "Default")
      (node (ref "U$1") (pin "P9.32") (pinfunction "VDD_ADC_P9.32") (pintype "bidirectional"))
    )
    (net (code "109") (name "unconnected-(U1-MCLR*-Pad18)") (class "Default")
      (node (ref "U1") (pin "18") (pinfunction "MCLR*_18") (pintype "input"))
    )
    (net (code "110") (name "unconnected-(U1-NC-Pad34)") (class "Default")
      (node (ref "U1") (pin "34") (pinfunction "NC_34") (pintype "no_connect"))
    )
    (net (code "111") (name "unconnected-(U1-NC_2-Pad12)") (class "Default")
      (node (ref "U1") (pin "12") (pinfunction "NC_2_12") (pintype "no_connect"))
    )
    (net (code "112") (name "unconnected-(U1-NC_3-Pad13)") (class "Default")
      (node (ref "U1") (pin "13") (pinfunction "NC_3_13") (pintype "no_connect"))
    )
    (net (code "113") (name "unconnected-(U1-NC_4-Pad33)") (class "Default")
      (node (ref "U1") (pin "33") (pinfunction "NC_4_33") (pintype "no_connect"))
    )
    (net (code "114") (name "unconnected-(U1-RA2-Pad21)") (class "Default")
      (node (ref "U1") (pin "21") (pinfunction "RA2_21") (pintype "bidirectional"))
    )
    (net (code "115") (name "unconnected-(U1-RA3-Pad22)") (class "Default")
      (node (ref "U1") (pin "22") (pinfunction "RA3_22") (pintype "bidirectional"))
    )
    (net (code "116") (name "unconnected-(U1-RA4-Pad23)") (class "Default")
      (node (ref "U1") (pin "23") (pinfunction "RA4_23") (pintype "bidirectional"))
    )
    (net (code "117") (name "unconnected-(U1-RA5-Pad24)") (class "Default")
      (node (ref "U1") (pin "24") (pinfunction "RA5_24") (pintype "bidirectional"))
    )
    (net (code "118") (name "unconnected-(U1-RA6-Pad31)") (class "Default")
      (node (ref "U1") (pin "31") (pinfunction "RA6_31") (pintype "bidirectional"))
    )
    (net (code "119") (name "unconnected-(U1-RA7-Pad30)") (class "Default")
      (node (ref "U1") (pin "30") (pinfunction "RA7_30") (pintype "bidirectional"))
    )
    (net (code "120") (name "unconnected-(U1-RB0-Pad8)") (class "Default")
      (node (ref "U1") (pin "8") (pinfunction "RB0_8") (pintype "bidirectional"))
    )
    (net (code "121") (name "unconnected-(U1-RB1-Pad9)") (class "Default")
      (node (ref "U1") (pin "9") (pinfunction "RB1_9") (pintype "bidirectional"))
    )
    (net (code "122") (name "unconnected-(U1-RB2-Pad10)") (class "Default")
      (node (ref "U1") (pin "10") (pinfunction "RB2_10") (pintype "bidirectional"))
    )
    (net (code "123") (name "unconnected-(U1-RB3-Pad11)") (class "Default")
      (node (ref "U1") (pin "11") (pinfunction "RB3_11") (pintype "bidirectional"))
    )
    (net (code "124") (name "unconnected-(U1-RB4-Pad14)") (class "Default")
      (node (ref "U1") (pin "14") (pinfunction "RB4_14") (pintype "bidirectional"))
    )
    (net (code "125") (name "unconnected-(U1-RB5-Pad15)") (class "Default")
      (node (ref "U1") (pin "15") (pinfunction "RB5_15") (pintype "bidirectional"))
    )
    (net (code "126") (name "unconnected-(U1-RB6-Pad16)") (class "Default")
      (node (ref "U1") (pin "16") (pinfunction "RB6_16") (pintype "bidirectional"))
    )
    (net (code "127") (name "unconnected-(U1-RB7-Pad17)") (class "Default")
      (node (ref "U1") (pin "17") (pinfunction "RB7_17") (pintype "bidirectional"))
    )
    (net (code "128") (name "unconnected-(U1-RC0-Pad32)") (class "Default")
      (node (ref "U1") (pin "32") (pinfunction "RC0_32") (pintype "bidirectional"))
    )
    (net (code "129") (name "unconnected-(U1-RC1-Pad35)") (class "Default")
      (node (ref "U1") (pin "35") (pinfunction "RC1_35") (pintype "bidirectional"))
    )
    (net (code "130") (name "unconnected-(U1-RC2-Pad36)") (class "Default")
      (node (ref "U1") (pin "36") (pinfunction "RC2_36") (pintype "bidirectional"))
    )
    (net (code "131") (name "unconnected-(U1-RC3-Pad37)") (class "Default")
      (node (ref "U1") (pin "37") (pinfunction "RC3_37") (pintype "bidirectional"))
    )
    (net (code "132") (name "unconnected-(U1-RC4-Pad42)") (class "Default")
      (node (ref "U1") (pin "42") (pinfunction "RC4_42") (pintype "bidirectional"))
    )
    (net (code "133") (name "unconnected-(U1-RC5-Pad43)") (class "Default")
      (node (ref "U1") (pin "43") (pinfunction "RC5_43") (pintype "bidirectional"))
    )
    (net (code "134") (name "unconnected-(U1-RC6-Pad44)") (class "Default")
      (node (ref "U1") (pin "44") (pinfunction "RC6_44") (pintype "bidirectional"))
    )
    (net (code "135") (name "unconnected-(U1-RD0-Pad38)") (class "Default")
      (node (ref "U1") (pin "38") (pinfunction "RD0_38") (pintype "bidirectional"))
    )
    (net (code "136") (name "unconnected-(U1-RD1-Pad39)") (class "Default")
      (node (ref "U1") (pin "39") (pinfunction "RD1_39") (pintype "bidirectional"))
    )
    (net (code "137") (name "unconnected-(U1-RD2-Pad40)") (class "Default")
      (node (ref "U1") (pin "40") (pinfunction "RD2_40") (pintype "bidirectional"))
    )
    (net (code "138") (name "unconnected-(U1-RD3-Pad41)") (class "Default")
      (node (ref "U1") (pin "41") (pinfunction "RD3_41") (pintype "bidirectional"))
    )
    (net (code "139") (name "unconnected-(U1-RD4-Pad2)") (class "Default")
      (node (ref "U1") (pin "2") (pinfunction "RD4_2") (pintype "bidirectional"))
    )
    (net (code "140") (name "unconnected-(U1-RD5-Pad3)") (class "Default")
      (node (ref "U1") (pin "3") (pinfunction "RD5_3") (pintype "bidirectional"))
    )
    (net (code "141") (name "unconnected-(U1-RD6-Pad4)") (class "Default")
      (node (ref "U1") (pin "4") (pinfunction "RD6_4") (pintype "bidirectional"))
    )
    (net (code "142") (name "unconnected-(U1-RE0-Pad25)") (class "Default")
      (node (ref "U1") (pin "25") (pinfunction "RE0_25") (pintype "bidirectional"))
    )
    (net (code "143") (name "unconnected-(U1-RE1-Pad26)") (class "Default")
      (node (ref "U1") (pin "26") (pinfunction "RE1_26") (pintype "bidirectional"))
    )
    (net (code "144") (name "unconnected-(U1-RE2-Pad27)") (class "Default")
      (node (ref "U1") (pin "27") (pinfunction "RE2_27") (pintype "bidirectional"))
    )
  )
)
